# Esquematico.net
KiCad netlist of a schematic drawn in EAGLE
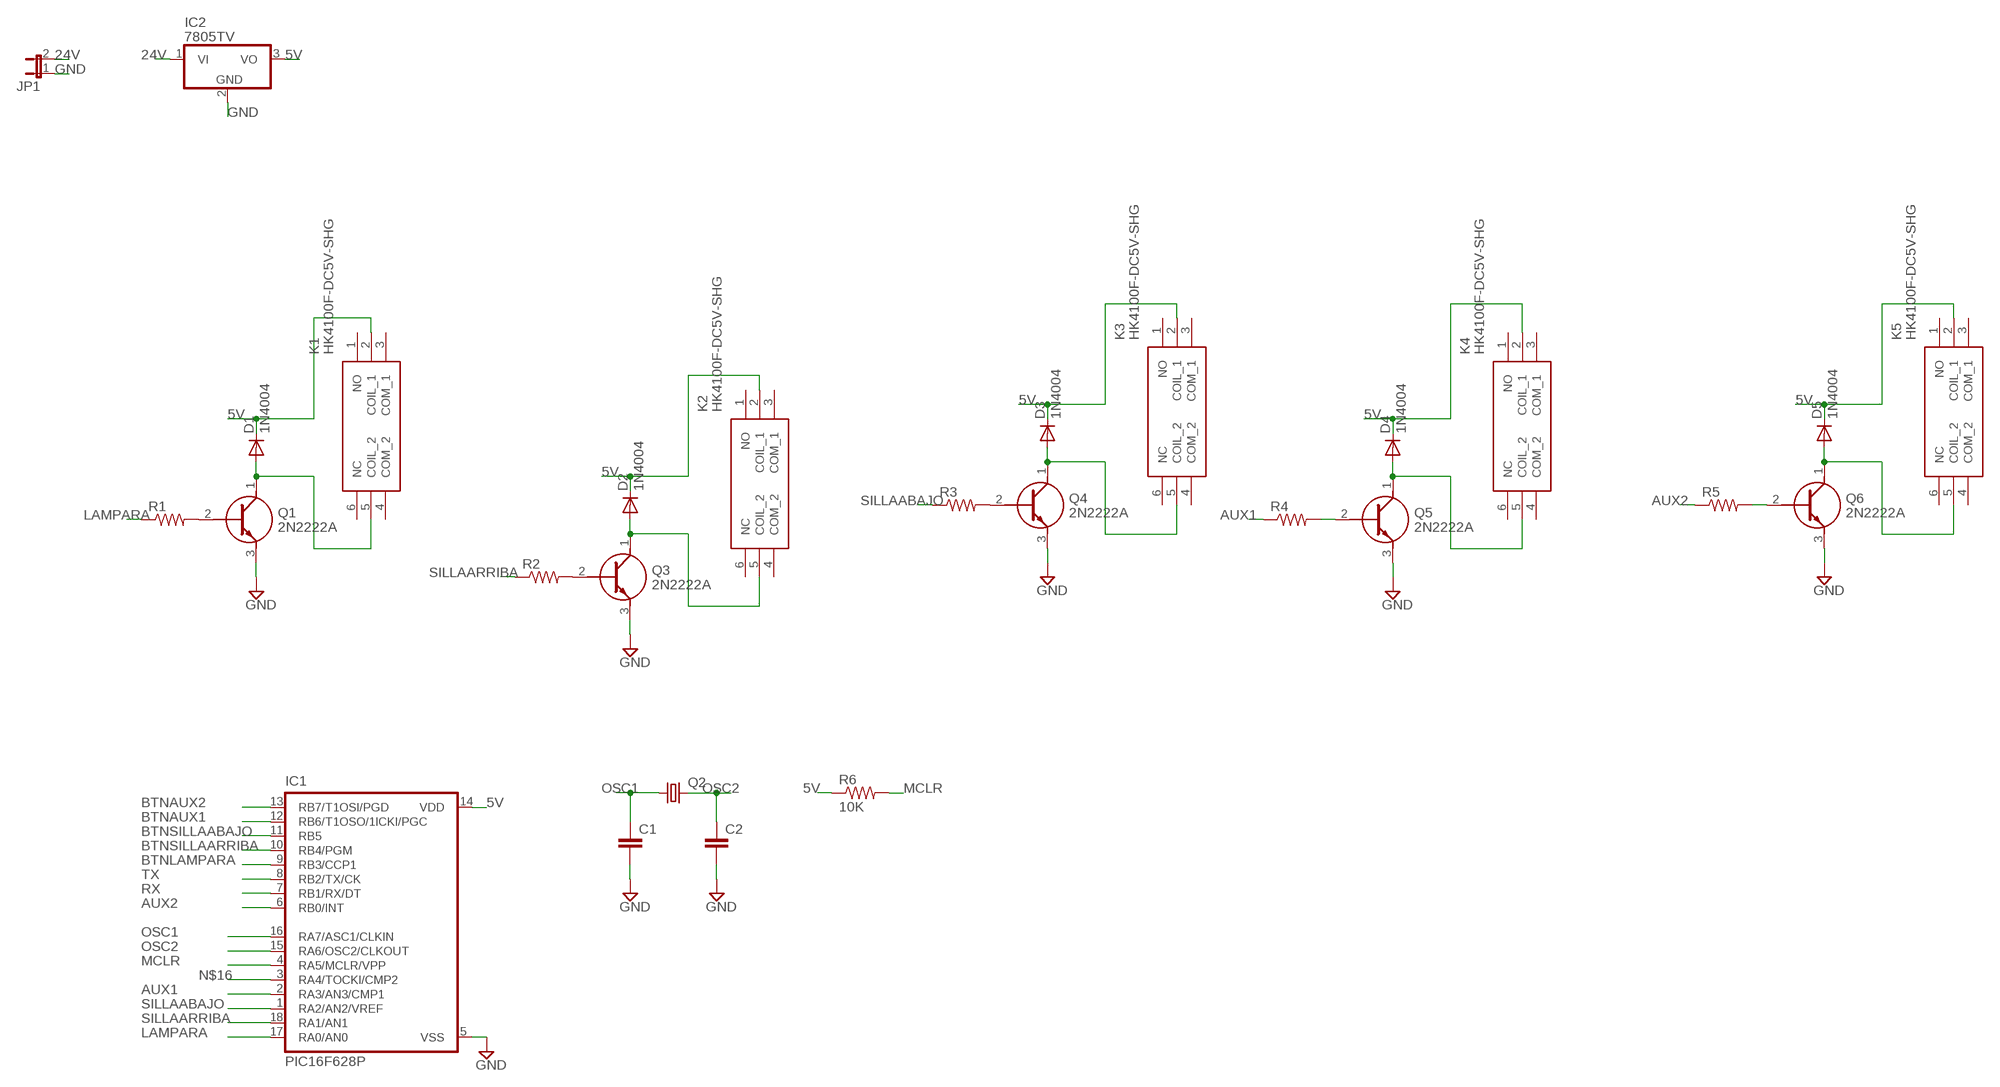
[diagram p0: schematic, sheet 1]

(export (version "E")
  (design (tool "Eeschema 10.0.6"))
  (components
    (comp (ref "C1")
      (value "C2,5-3")
      (footprint "eagle-import:C2.5-3")
      (libsource (lib "eagle-import") (part "C2,5-3"))
    )
    (comp (ref "C2")
      (value "C2,5-3")
      (footprint "eagle-import:C2.5-3")
      (libsource (lib "eagle-import") (part "C2,5-3"))
    )
    (comp (ref "D1")
      (value "1N4004")
      (footprint "eagle-import:DO41-10")
      (libsource (lib "eagle-import") (part "1N4004"))
    )
    (comp (ref "D2")
      (value "1N4004")
      (footprint "eagle-import:DO41-10")
      (libsource (lib "eagle-import") (part "1N4004"))
    )
    (comp (ref "D3")
      (value "1N4004")
      (footprint "eagle-import:DO41-10")
      (libsource (lib "eagle-import") (part "1N4004"))
    )
    (comp (ref "D4")
      (value "1N4004")
      (footprint "eagle-import:DO41-10")
      (libsource (lib "eagle-import") (part "1N4004"))
    )
    (comp (ref "D5")
      (value "1N4004")
      (footprint "eagle-import:DO41-10")
      (libsource (lib "eagle-import") (part "1N4004"))
    )
    (comp (ref "IC1")
      (value "PIC16F628P")
      (footprint "eagle-import:DIL18")
      (fields (field (name "MF") "MICROCHIP") (field (name "MPN") "PIC16F628-20/P"))
      (libsource (lib "eagle-import") (part "PIC16F628P"))
    )
    (comp (ref "IC2")
      (value "7805TV")
      (footprint "eagle-import:TO220V")
      (libsource (lib "eagle-import") (part "78TV05"))
    )
    (comp (ref "JP1")
      (value "JP1E")
      (footprint "eagle-import:JP1")
      (libsource (lib "eagle-import") (part "JP1E"))
    )
    (comp (ref "K1")
      (value "HK4100F-DC5V-SHG")
      (footprint "eagle-import:HK4100FDC5VSHG")
      (libsource (lib "eagle-import") (part "HK4100F-DC5V-SHG"))
    )
    (comp (ref "K2")
      (value "HK4100F-DC5V-SHG")
      (footprint "eagle-import:HK4100FDC5VSHG")
      (libsource (lib "eagle-import") (part "HK4100F-DC5V-SHG"))
    )
    (comp (ref "K3")
      (value "HK4100F-DC5V-SHG")
      (footprint "eagle-import:HK4100FDC5VSHG")
      (libsource (lib "eagle-import") (part "HK4100F-DC5V-SHG"))
    )
    (comp (ref "K4")
      (value "HK4100F-DC5V-SHG")
      (footprint "eagle-import:HK4100FDC5VSHG")
      (libsource (lib "eagle-import") (part "HK4100F-DC5V-SHG"))
    )
    (comp (ref "K5")
      (value "HK4100F-DC5V-SHG")
      (footprint "eagle-import:HK4100FDC5VSHG")
      (libsource (lib "eagle-import") (part "HK4100F-DC5V-SHG"))
    )
    (comp (ref "Q1")
      (value "2N2222A")
      (footprint "eagle-import:2N2222A")
      (libsource (lib "eagle-import") (part "2N2222A"))
    )
    (comp (ref "Q2")
      (value "CRYSTALHC49U70")
      (footprint "eagle-import:HC49U70")
      (libsource (lib "eagle-import") (part "CRYSTALHC49U70"))
    )
    (comp (ref "Q3")
      (value "2N2222A")
      (footprint "eagle-import:2N2222A")
      (libsource (lib "eagle-import") (part "2N2222A"))
    )
    (comp (ref "Q4")
      (value "2N2222A")
      (footprint "eagle-import:2N2222A")
      (libsource (lib "eagle-import") (part "2N2222A"))
    )
    (comp (ref "Q5")
      (value "2N2222A")
      (footprint "eagle-import:2N2222A")
      (libsource (lib "eagle-import") (part "2N2222A"))
    )
    (comp (ref "Q6")
      (value "2N2222A")
      (footprint "eagle-import:2N2222A")
      (libsource (lib "eagle-import") (part "2N2222A"))
    )
    (comp (ref "R1")
      (value "R-US_0207/7")
      (footprint "eagle-import:0207_7")
      (libsource (lib "eagle-import") (part "R-US_0207/7"))
    )
    (comp (ref "R2")
      (value "R-US_0207/7")
      (footprint "eagle-import:0207_7")
      (libsource (lib "eagle-import") (part "R-US_0207/7"))
    )
    (comp (ref "R3")
      (value "R-US_0207/7")
      (footprint "eagle-import:0207_7")
      (libsource (lib "eagle-import") (part "R-US_0207/7"))
    )
    (comp (ref "R4")
      (value "R-US_0207/7")
      (footprint "eagle-import:0207_7")
      (libsource (lib "eagle-import") (part "R-US_0207/7"))
    )
    (comp (ref "R5")
      (value "R-US_0207/7")
      (footprint "eagle-import:0207_7")
      (libsource (lib "eagle-import") (part "R-US_0207/7"))
    )
    (comp (ref "R6")
      (value "10K")
      (footprint "eagle-import:0207_7")
      (libsource (lib "eagle-import") (part "R-US_0207/7"))
    )
  )
  (nets
    (net (code "1") (name "/5V") (class "Default")
      (node (ref "D1") (pin "C") (pinfunction "C_C") (pintype "passive"))
      (node (ref "D2") (pin "C") (pinfunction "C_C") (pintype "passive"))
      (node (ref "D3") (pin "C") (pinfunction "C_C") (pintype "passive"))
      (node (ref "D4") (pin "C") (pinfunction "C_C") (pintype "passive"))
      (node (ref "D5") (pin "C") (pinfunction "C_C") (pintype "passive"))
      (node (ref "IC1") (pin "14") (pinfunction "VDD_14") (pintype "power_in"))
      (node (ref "IC2") (pin "3") (pinfunction "VO_3") (pintype "passive"))
      (node (ref "K1") (pin "2") (pinfunction "COIL_1_2") (pintype "bidirectional"))
      (node (ref "K2") (pin "2") (pinfunction "COIL_1_2") (pintype "bidirectional"))
      (node (ref "K3") (pin "2") (pinfunction "COIL_1_2") (pintype "bidirectional"))
      (node (ref "K4") (pin "2") (pinfunction "COIL_1_2") (pintype "bidirectional"))
      (node (ref "K5") (pin "2") (pinfunction "COIL_1_2") (pintype "bidirectional"))
      (node (ref "R6") (pin "1") (pinfunction "1_1") (pintype "passive"))
    )
    (net (code "2") (name "/24V") (class "Default")
      (node (ref "IC2") (pin "1") (pinfunction "VI_1") (pintype "input"))
      (node (ref "JP1") (pin "2") (pinfunction "2_2") (pintype "passive"))
    )
    (net (code "3") (name "/AUX1") (class "Default")
      (node (ref "IC1") (pin "2") (pinfunction "RA3/AN3/CMP1_2") (pintype "bidirectional"))
      (node (ref "R4") (pin "1") (pinfunction "1_1") (pintype "passive"))
    )
    (net (code "4") (name "/AUX2") (class "Default")
      (node (ref "IC1") (pin "6") (pinfunction "RB0/INT_6") (pintype "bidirectional"))
      (node (ref "R5") (pin "1") (pinfunction "1_1") (pintype "passive"))
    )
    (net (code "5") (name "/BTNAUX1") (class "Default")
      (node (ref "IC1") (pin "12") (pinfunction "RB6/T1OSO/1ICKI/PGC_12") (pintype "bidirectional"))
    )
    (net (code "6") (name "/BTNAUX2") (class "Default")
      (node (ref "IC1") (pin "13") (pinfunction "RB7/T1OSI/PGD_13") (pintype "bidirectional"))
    )
    (net (code "7") (name "/BTNLAMPARA") (class "Default")
      (node (ref "IC1") (pin "9") (pinfunction "RB3/CCP1_9") (pintype "bidirectional"))
    )
    (net (code "8") (name "/BTNSILLAABAJO") (class "Default")
      (node (ref "IC1") (pin "11") (pinfunction "RB5_11") (pintype "bidirectional"))
    )
    (net (code "9") (name "/BTNSILLAARRIBA") (class "Default")
      (node (ref "IC1") (pin "10") (pinfunction "RB4/PGM_10") (pintype "bidirectional"))
    )
    (net (code "10") (name "/LAMPARA") (class "Default")
      (node (ref "IC1") (pin "17") (pinfunction "RA0/AN0_17") (pintype "bidirectional"))
      (node (ref "R1") (pin "1") (pinfunction "1_1") (pintype "passive"))
    )
    (net (code "11") (name "/MCLR") (class "Default")
      (node (ref "IC1") (pin "4") (pinfunction "RA5/MCLR/VPP_4") (pintype "input"))
      (node (ref "R6") (pin "2") (pinfunction "2_2") (pintype "passive"))
    )
    (net (code "12") (name "/N$16") (class "Default")
      (node (ref "IC1") (pin "3") (pinfunction "RA4/TOCKI/CMP2_3") (pintype "bidirectional"))
    )
    (net (code "13") (name "/OSC1") (class "Default")
      (node (ref "C1") (pin "1") (pinfunction "1_1") (pintype "passive"))
      (node (ref "IC1") (pin "16") (pinfunction "RA7/ASC1/CLKIN_16") (pintype "bidirectional"))
      (node (ref "Q2") (pin "1") (pinfunction "1_1") (pintype "passive"))
    )
    (net (code "14") (name "/OSC2") (class "Default")
      (node (ref "C2") (pin "1") (pinfunction "1_1") (pintype "passive"))
      (node (ref "IC1") (pin "15") (pinfunction "RA6/OSC2/CLKOUT_15") (pintype "bidirectional"))
      (node (ref "Q2") (pin "2") (pinfunction "2_2") (pintype "passive"))
    )
    (net (code "15") (name "/RX") (class "Default")
      (node (ref "IC1") (pin "7") (pinfunction "RB1/RX/DT_7") (pintype "bidirectional"))
    )
    (net (code "16") (name "/SILLAABAJO") (class "Default")
      (node (ref "IC1") (pin "1") (pinfunction "RA2/AN2/VREF_1") (pintype "bidirectional"))
      (node (ref "R3") (pin "1") (pinfunction "1_1") (pintype "passive"))
    )
    (net (code "17") (name "/SILLAARRIBA") (class "Default")
      (node (ref "IC1") (pin "18") (pinfunction "RA1/AN1_18") (pintype "bidirectional"))
      (node (ref "R2") (pin "1") (pinfunction "1_1") (pintype "passive"))
    )
    (net (code "18") (name "/TX") (class "Default")
      (node (ref "IC1") (pin "8") (pinfunction "RB2/TX/CK_8") (pintype "bidirectional"))
    )
    (net (code "19") (name "GND") (class "Default")
      (node (ref "C1") (pin "2") (pinfunction "2_2") (pintype "passive"))
      (node (ref "C2") (pin "2") (pinfunction "2_2") (pintype "passive"))
      (node (ref "IC1") (pin "5") (pinfunction "VSS_5") (pintype "power_in"))
      (node (ref "IC2") (pin "2") (pinfunction "GND_2") (pintype "passive"))
      (node (ref "JP1") (pin "1") (pinfunction "1_1") (pintype "passive"))
      (node (ref "Q1") (pin "3") (pinfunction "E_3") (pintype "bidirectional"))
      (node (ref "Q3") (pin "3") (pinfunction "E_3") (pintype "bidirectional"))
      (node (ref "Q4") (pin "3") (pinfunction "E_3") (pintype "bidirectional"))
      (node (ref "Q5") (pin "3") (pinfunction "E_3") (pintype "bidirectional"))
      (node (ref "Q6") (pin "3") (pinfunction "E_3") (pintype "bidirectional"))
    )
    (net (code "20") (name "Net-(K1-COIL_2)") (class "Default")
      (node (ref "D1") (pin "A") (pinfunction "A_A") (pintype "passive"))
      (node (ref "K1") (pin "5") (pinfunction "COIL_2_5") (pintype "bidirectional"))
      (node (ref "Q1") (pin "1") (pinfunction "C_1") (pintype "bidirectional"))
    )
    (net (code "21") (name "Net-(K2-COIL_2)") (class "Default")
      (node (ref "D2") (pin "A") (pinfunction "A_A") (pintype "passive"))
      (node (ref "K2") (pin "5") (pinfunction "COIL_2_5") (pintype "bidirectional"))
      (node (ref "Q3") (pin "1") (pinfunction "C_1") (pintype "bidirectional"))
    )
    (net (code "22") (name "Net-(K3-COIL_2)") (class "Default")
      (node (ref "D3") (pin "A") (pinfunction "A_A") (pintype "passive"))
      (node (ref "K3") (pin "5") (pinfunction "COIL_2_5") (pintype "bidirectional"))
      (node (ref "Q4") (pin "1") (pinfunction "C_1") (pintype "bidirectional"))
    )
    (net (code "23") (name "Net-(K4-COIL_2)") (class "Default")
      (node (ref "D4") (pin "A") (pinfunction "A_A") (pintype "passive"))
      (node (ref "K4") (pin "5") (pinfunction "COIL_2_5") (pintype "bidirectional"))
      (node (ref "Q5") (pin "1") (pinfunction "C_1") (pintype "bidirectional"))
    )
    (net (code "24") (name "Net-(K5-COIL_2)") (class "Default")
      (node (ref "D5") (pin "A") (pinfunction "A_A") (pintype "passive"))
      (node (ref "K5") (pin "5") (pinfunction "COIL_2_5") (pintype "bidirectional"))
      (node (ref "Q6") (pin "1") (pinfunction "C_1") (pintype "bidirectional"))
    )
    (net (code "25") (name "Net-(Q1-B)") (class "Default")
      (node (ref "Q1") (pin "2") (pinfunction "B_2") (pintype "bidirectional"))
      (node (ref "R1") (pin "2") (pinfunction "2_2") (pintype "passive"))
    )
    (net (code "26") (name "Net-(Q3-B)") (class "Default")
      (node (ref "Q3") (pin "2") (pinfunction "B_2") (pintype "bidirectional"))
      (node (ref "R2") (pin "2") (pinfunction "2_2") (pintype "passive"))
    )
    (net (code "27") (name "Net-(Q4-B)") (class "Default")
      (node (ref "Q4") (pin "2") (pinfunction "B_2") (pintype "bidirectional"))
      (node (ref "R3") (pin "2") (pinfunction "2_2") (pintype "passive"))
    )
    (net (code "28") (name "Net-(Q5-B)") (class "Default")
      (node (ref "Q5") (pin "2") (pinfunction "B_2") (pintype "bidirectional"))
      (node (ref "R4") (pin "2") (pinfunction "2_2") (pintype "passive"))
    )
    (net (code "29") (name "Net-(Q6-B)") (class "Default")
      (node (ref "Q6") (pin "2") (pinfunction "B_2") (pintype "bidirectional"))
      (node (ref "R5") (pin "2") (pinfunction "2_2") (pintype "passive"))
    )
    (net (code "30") (name "unconnected-(K1-COM_1-Pad3)") (class "Default")
      (node (ref "K1") (pin "3") (pinfunction "COM_1_3") (pintype "bidirectional"))
    )
    (net (code "31") (name "unconnected-(K1-COM_2-Pad4)") (class "Default")
      (node (ref "K1") (pin "4") (pinfunction "COM_2_4") (pintype "bidirectional"))
    )
    (net (code "32") (name "unconnected-(K1-NC-Pad6)") (class "Default")
      (node (ref "K1") (pin "6") (pinfunction "NC_6") (pintype "no_connect"))
    )
    (net (code "33") (name "unconnected-(K1-NO-Pad1)") (class "Default")
      (node (ref "K1") (pin "1") (pinfunction "NO_1") (pintype "bidirectional"))
    )
    (net (code "34") (name "unconnected-(K2-COM_1-Pad3)") (class "Default")
      (node (ref "K2") (pin "3") (pinfunction "COM_1_3") (pintype "bidirectional"))
    )
    (net (code "35") (name "unconnected-(K2-COM_2-Pad4)") (class "Default")
      (node (ref "K2") (pin "4") (pinfunction "COM_2_4") (pintype "bidirectional"))
    )
    (net (code "36") (name "unconnected-(K2-NC-Pad6)") (class "Default")
      (node (ref "K2") (pin "6") (pinfunction "NC_6") (pintype "no_connect"))
    )
    (net (code "37") (name "unconnected-(K2-NO-Pad1)") (class "Default")
      (node (ref "K2") (pin "1") (pinfunction "NO_1") (pintype "bidirectional"))
    )
    (net (code "38") (name "unconnected-(K3-COM_1-Pad3)") (class "Default")
      (node (ref "K3") (pin "3") (pinfunction "COM_1_3") (pintype "bidirectional"))
    )
    (net (code "39") (name "unconnected-(K3-COM_2-Pad4)") (class "Default")
      (node (ref "K3") (pin "4") (pinfunction "COM_2_4") (pintype "bidirectional"))
    )
    (net (code "40") (name "unconnected-(K3-NC-Pad6)") (class "Default")
      (node (ref "K3") (pin "6") (pinfunction "NC_6") (pintype "no_connect"))
    )
    (net (code "41") (name "unconnected-(K3-NO-Pad1)") (class "Default")
      (node (ref "K3") (pin "1") (pinfunction "NO_1") (pintype "bidirectional"))
    )
    (net (code "42") (name "unconnected-(K4-COM_1-Pad3)") (class "Default")
      (node (ref "K4") (pin "3") (pinfunction "COM_1_3") (pintype "bidirectional"))
    )
    (net (code "43") (name "unconnected-(K4-COM_2-Pad4)") (class "Default")
      (node (ref "K4") (pin "4") (pinfunction "COM_2_4") (pintype "bidirectional"))
    )
    (net (code "44") (name "unconnected-(K4-NC-Pad6)") (class "Default")
      (node (ref "K4") (pin "6") (pinfunction "NC_6") (pintype "no_connect"))
    )
    (net (code "45") (name "unconnected-(K4-NO-Pad1)") (class "Default")
      (node (ref "K4") (pin "1") (pinfunction "NO_1") (pintype "bidirectional"))
    )
    (net (code "46") (name "unconnected-(K5-COM_1-Pad3)") (class "Default")
      (node (ref "K5") (pin "3") (pinfunction "COM_1_3") (pintype "bidirectional"))
    )
    (net (code "47") (name "unconnected-(K5-COM_2-Pad4)") (class "Default")
      (node (ref "K5") (pin "4") (pinfunction "COM_2_4") (pintype "bidirectional"))
    )
    (net (code "48") (name "unconnected-(K5-NC-Pad6)") (class "Default")
      (node (ref "K5") (pin "6") (pinfunction "NC_6") (pintype "no_connect"))
    )
    (net (code "49") (name "unconnected-(K5-NO-Pad1)") (class "Default")
      (node (ref "K5") (pin "1") (pinfunction "NO_1") (pintype "bidirectional"))
    )
  )
)
